# 2-_balenaFin_HAT_SCH.net
KiCad netlist of a schematic drawn in Altium Designer
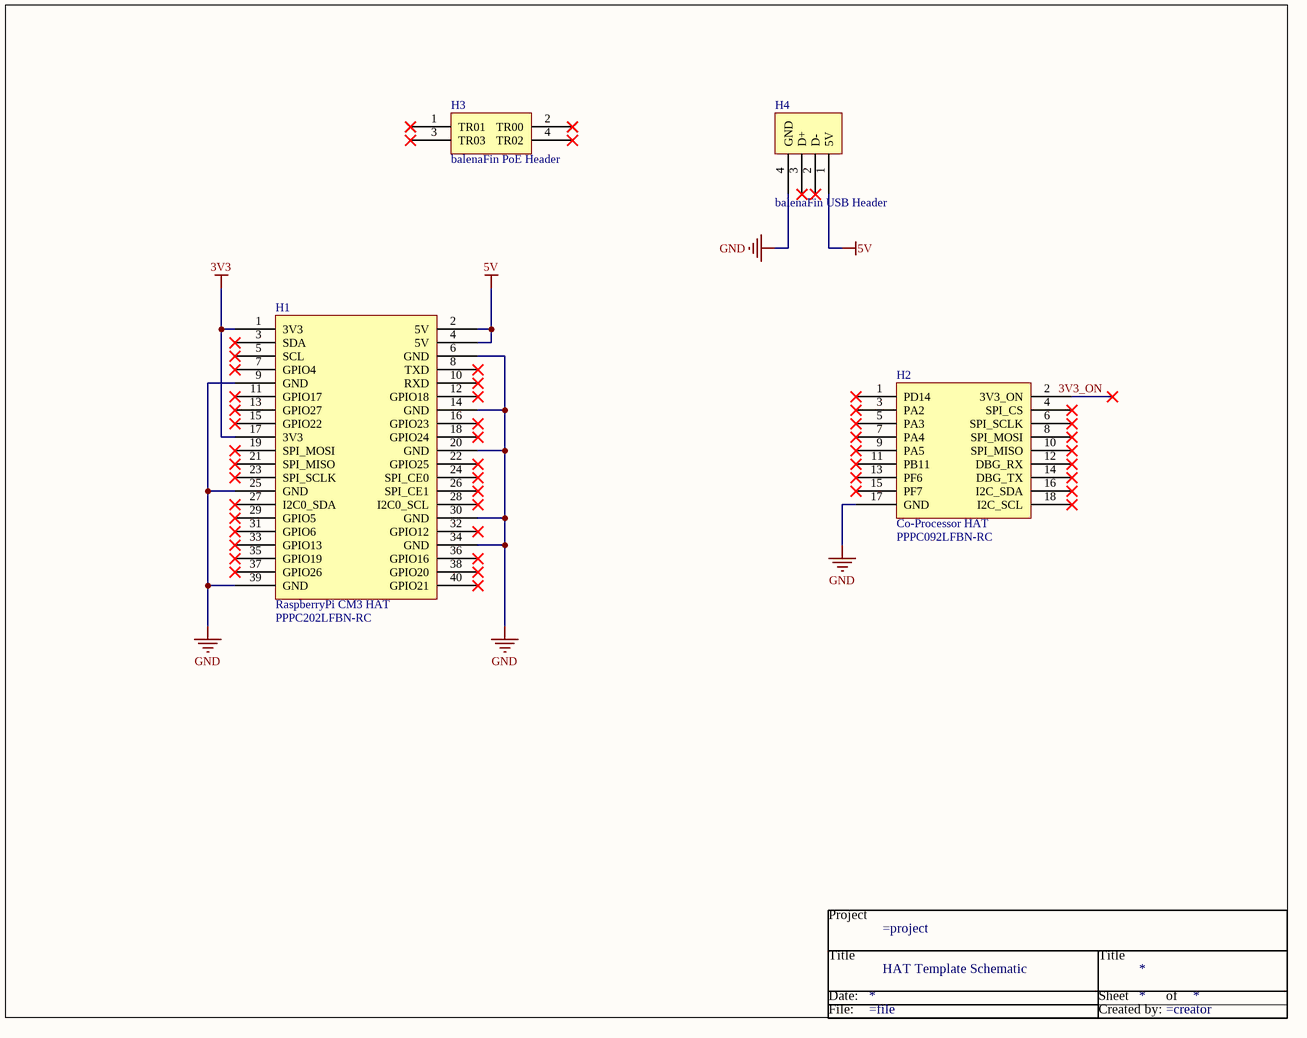
[diagram p0: 2- balenaFin HAT SCH.SchDoc]

(export (version "E")
  (design (tool "Eeschema 10.0.6"))
  (components
    (comp (ref "*") (value "Title_Block") (libsource (lib "balenaPerf schlib") (part "Title_Block")))
    (comp (ref "H1")
      (value "RaspberryPi CM3 HAT")
      (footprint "HDR2x20_2mm54")
      (description "Raspberry Pi CM3 HAT Socket")
      (fields
        (field (name "MANUFACTURER") "Sullins")
        (field (name "MANUFACTURER PART NUMBER") "PPPC202LFBN-RC")
        (field (name "SUPPLIER PART NUMBER 1") "PPPC202LFBN-RC")
      )
      (libsource (lib "balenaPerf schlib") (part "CM3_Header"))
    )
    (comp (ref "H2")
      (value "Co-Processor HAT")
      (footprint "HDR2x9_2mm54")
      (description "balenaFin Co-Processor HAT Socket")
      (fields
        (field (name "MANUFACTURER") "Sullins")
        (field (name "MANUFACTURER PART NUMBER") "PPPC092LFBN-RC")
      )
      (libsource (lib "balenaPerf schlib") (part "COP_Header"))
    )
    (comp (ref "H3")
      (value "balenaFin PoE Header")
      (footprint "HDR2x2_2mm54")
      (fields
        (field (name "MANUFACTURER") "Sullins")
        (field (name "MANUFACTURER PART NUMBER") "PPPC022LFBN-RC")
      )
      (libsource (lib "balenaPerf schlib") (part "POE_Header"))
    )
    (comp (ref "H4")
      (value "balenaFin USB Header")
      (footprint "HDR1x4_2mm54")
      (fields
        (field (name "MANUFACTURER") "Sullins")
        (field (name "MANUFACTURER PART NUMBER") "PPPC041LFBN-RC")
      )
      (libsource (lib "balenaPerf schlib") (part "USB_Header"))
    )
  )
  (nets
    (net (code "2") (name "3V3") (class "Default")
      (node (ref "H1") (pin "1") (pinfunction "3V3_1") (pintype "passive"))
      (node (ref "H1") (pin "17") (pinfunction "3V3_17") (pintype "passive"))
    )
    (net (code "3") (name "5V") (class "Default")
      (node (ref "H1") (pin "2") (pinfunction "5V_2") (pintype "passive"))
      (node (ref "H1") (pin "4") (pinfunction "5V_4") (pintype "passive"))
      (node (ref "H4") (pin "1") (pinfunction "5V_1") (pintype "passive"))
    )
    (net (code "4") (name "GND") (class "Default")
      (node (ref "H1") (pin "14") (pinfunction "GND_14") (pintype "passive"))
      (node (ref "H1") (pin "20") (pinfunction "GND_20") (pintype "passive"))
      (node (ref "H1") (pin "25") (pinfunction "GND_25") (pintype "passive"))
      (node (ref "H1") (pin "30") (pinfunction "GND_30") (pintype "passive"))
      (node (ref "H1") (pin "34") (pinfunction "GND_34") (pintype "passive"))
      (node (ref "H1") (pin "39") (pinfunction "GND_39") (pintype "passive"))
      (node (ref "H1") (pin "6") (pinfunction "GND_6") (pintype "passive"))
      (node (ref "H1") (pin "9") (pinfunction "GND_9") (pintype "passive"))
      (node (ref "H2") (pin "17") (pinfunction "GND_17") (pintype "passive"))
      (node (ref "H4") (pin "4") (pinfunction "GND_4") (pintype "passive"))
    )
    (net (code "5") (name "unconnected-(H1-GPIO4-Pad7)") (class "Default")
      (node (ref "H1") (pin "7") (pinfunction "GPIO4_7") (pintype "passive+no_connect"))
    )
    (net (code "6") (name "unconnected-(H1-GPIO5-Pad29)") (class "Default")
      (node (ref "H1") (pin "29") (pinfunction "GPIO5_29") (pintype "passive+no_connect"))
    )
    (net (code "7") (name "unconnected-(H1-GPIO6-Pad31)") (class "Default")
      (node (ref "H1") (pin "31") (pinfunction "GPIO6_31") (pintype "passive+no_connect"))
    )
    (net (code "8") (name "unconnected-(H1-GPIO12-Pad32)") (class "Default")
      (node (ref "H1") (pin "32") (pinfunction "GPIO12_32") (pintype "passive+no_connect"))
    )
    (net (code "9") (name "unconnected-(H1-GPIO13-Pad33)") (class "Default")
      (node (ref "H1") (pin "33") (pinfunction "GPIO13_33") (pintype "passive+no_connect"))
    )
    (net (code "10") (name "unconnected-(H1-GPIO16-Pad36)") (class "Default")
      (node (ref "H1") (pin "36") (pinfunction "GPIO16_36") (pintype "passive+no_connect"))
    )
    (net (code "11") (name "unconnected-(H1-GPIO17-Pad11)") (class "Default")
      (node (ref "H1") (pin "11") (pinfunction "GPIO17_11") (pintype "passive+no_connect"))
    )
    (net (code "12") (name "unconnected-(H1-GPIO18-Pad12)") (class "Default")
      (node (ref "H1") (pin "12") (pinfunction "GPIO18_12") (pintype "passive+no_connect"))
    )
    (net (code "13") (name "unconnected-(H1-GPIO19-Pad35)") (class "Default")
      (node (ref "H1") (pin "35") (pinfunction "GPIO19_35") (pintype "passive+no_connect"))
    )
    (net (code "14") (name "unconnected-(H1-GPIO20-Pad38)") (class "Default")
      (node (ref "H1") (pin "38") (pinfunction "GPIO20_38") (pintype "passive+no_connect"))
    )
    (net (code "15") (name "unconnected-(H1-GPIO21-Pad40)") (class "Default")
      (node (ref "H1") (pin "40") (pinfunction "GPIO21_40") (pintype "passive+no_connect"))
    )
    (net (code "16") (name "unconnected-(H1-GPIO22-Pad15)") (class "Default")
      (node (ref "H1") (pin "15") (pinfunction "GPIO22_15") (pintype "passive+no_connect"))
    )
    (net (code "17") (name "unconnected-(H1-GPIO23-Pad16)") (class "Default")
      (node (ref "H1") (pin "16") (pinfunction "GPIO23_16") (pintype "passive+no_connect"))
    )
    (net (code "18") (name "unconnected-(H1-GPIO24-Pad18)") (class "Default")
      (node (ref "H1") (pin "18") (pinfunction "GPIO24_18") (pintype "passive+no_connect"))
    )
    (net (code "19") (name "unconnected-(H1-GPIO25-Pad22)") (class "Default")
      (node (ref "H1") (pin "22") (pinfunction "GPIO25_22") (pintype "passive+no_connect"))
    )
    (net (code "20") (name "unconnected-(H1-GPIO26-Pad37)") (class "Default")
      (node (ref "H1") (pin "37") (pinfunction "GPIO26_37") (pintype "passive+no_connect"))
    )
    (net (code "21") (name "unconnected-(H1-GPIO27-Pad13)") (class "Default")
      (node (ref "H1") (pin "13") (pinfunction "GPIO27_13") (pintype "passive+no_connect"))
    )
    (net (code "22") (name "unconnected-(H1-I2C0_SCL-Pad28)") (class "Default")
      (node (ref "H1") (pin "28") (pinfunction "I2C0_SCL_28") (pintype "passive+no_connect"))
    )
    (net (code "23") (name "unconnected-(H1-I2C0_SDA-Pad27)") (class "Default")
      (node (ref "H1") (pin "27") (pinfunction "I2C0_SDA_27") (pintype "passive+no_connect"))
    )
    (net (code "24") (name "unconnected-(H1-RXD-Pad10)") (class "Default")
      (node (ref "H1") (pin "10") (pinfunction "RXD_10") (pintype "passive+no_connect"))
    )
    (net (code "25") (name "unconnected-(H1-SCL-Pad5)") (class "Default")
      (node (ref "H1") (pin "5") (pinfunction "SCL_5") (pintype "passive+no_connect"))
    )
    (net (code "26") (name "unconnected-(H1-SDA-Pad3)") (class "Default")
      (node (ref "H1") (pin "3") (pinfunction "SDA_3") (pintype "passive+no_connect"))
    )
    (net (code "27") (name "unconnected-(H1-SPI_CE0-Pad24)") (class "Default")
      (node (ref "H1") (pin "24") (pinfunction "SPI_CE0_24") (pintype "passive+no_connect"))
    )
    (net (code "28") (name "unconnected-(H1-SPI_CE1-Pad26)") (class "Default")
      (node (ref "H1") (pin "26") (pinfunction "SPI_CE1_26") (pintype "passive+no_connect"))
    )
    (net (code "29") (name "unconnected-(H1-SPI_MISO-Pad21)") (class "Default")
      (node (ref "H1") (pin "21") (pinfunction "SPI_MISO_21") (pintype "passive+no_connect"))
    )
    (net (code "30") (name "unconnected-(H1-SPI_MOSI-Pad19)") (class "Default")
      (node (ref "H1") (pin "19") (pinfunction "SPI_MOSI_19") (pintype "passive+no_connect"))
    )
    (net (code "31") (name "unconnected-(H1-SPI_SCLK-Pad23)") (class "Default")
      (node (ref "H1") (pin "23") (pinfunction "SPI_SCLK_23") (pintype "passive+no_connect"))
    )
    (net (code "32") (name "unconnected-(H1-TXD-Pad8)") (class "Default")
      (node (ref "H1") (pin "8") (pinfunction "TXD_8") (pintype "passive+no_connect"))
    )
    (net (code "33") (name "unconnected-(H2-3V3_ON-Pad2)") (class "Default")
      (node (ref "H2") (pin "2") (pinfunction "3V3_ON_2") (pintype "passive+no_connect"))
    )
    (net (code "34") (name "unconnected-(H2-DBG_RX-Pad12)") (class "Default")
      (node (ref "H2") (pin "12") (pinfunction "DBG_RX_12") (pintype "passive+no_connect"))
    )
    (net (code "35") (name "unconnected-(H2-DBG_TX-Pad14)") (class "Default")
      (node (ref "H2") (pin "14") (pinfunction "DBG_TX_14") (pintype "passive+no_connect"))
    )
    (net (code "36") (name "unconnected-(H2-I2C_SCL-Pad18)") (class "Default")
      (node (ref "H2") (pin "18") (pinfunction "I2C_SCL_18") (pintype "passive+no_connect"))
    )
    (net (code "37") (name "unconnected-(H2-I2C_SDA-Pad16)") (class "Default")
      (node (ref "H2") (pin "16") (pinfunction "I2C_SDA_16") (pintype "passive+no_connect"))
    )
    (net (code "38") (name "unconnected-(H2-PA2-Pad3)") (class "Default")
      (node (ref "H2") (pin "3") (pinfunction "PA2_3") (pintype "passive+no_connect"))
    )
    (net (code "39") (name "unconnected-(H2-PA3-Pad5)") (class "Default")
      (node (ref "H2") (pin "5") (pinfunction "PA3_5") (pintype "passive+no_connect"))
    )
    (net (code "40") (name "unconnected-(H2-PA4-Pad7)") (class "Default")
      (node (ref "H2") (pin "7") (pinfunction "PA4_7") (pintype "passive+no_connect"))
    )
    (net (code "41") (name "unconnected-(H2-PA5-Pad9)") (class "Default")
      (node (ref "H2") (pin "9") (pinfunction "PA5_9") (pintype "passive+no_connect"))
    )
    (net (code "42") (name "unconnected-(H2-PB11-Pad11)") (class "Default")
      (node (ref "H2") (pin "11") (pinfunction "PB11_11") (pintype "passive+no_connect"))
    )
    (net (code "43") (name "unconnected-(H2-PD14-Pad1)") (class "Default")
      (node (ref "H2") (pin "1") (pinfunction "PD14_1") (pintype "passive+no_connect"))
    )
    (net (code "44") (name "unconnected-(H2-PF6-Pad13)") (class "Default")
      (node (ref "H2") (pin "13") (pinfunction "PF6_13") (pintype "passive+no_connect"))
    )
    (net (code "45") (name "unconnected-(H2-PF7-Pad15)") (class "Default")
      (node (ref "H2") (pin "15") (pinfunction "PF7_15") (pintype "passive+no_connect"))
    )
    (net (code "46") (name "unconnected-(H2-SPI_CS-Pad4)") (class "Default")
      (node (ref "H2") (pin "4") (pinfunction "SPI_CS_4") (pintype "passive+no_connect"))
    )
    (net (code "47") (name "unconnected-(H2-SPI_MISO-Pad10)") (class "Default")
      (node (ref "H2") (pin "10") (pinfunction "SPI_MISO_10") (pintype "passive+no_connect"))
    )
    (net (code "48") (name "unconnected-(H2-SPI_MOSI-Pad8)") (class "Default")
      (node (ref "H2") (pin "8") (pinfunction "SPI_MOSI_8") (pintype "passive+no_connect"))
    )
    (net (code "49") (name "unconnected-(H2-SPI_SCLK-Pad6)") (class "Default")
      (node (ref "H2") (pin "6") (pinfunction "SPI_SCLK_6") (pintype "passive+no_connect"))
    )
    (net (code "50") (name "unconnected-(H3-TR00-Pad2)") (class "Default")
      (node (ref "H3") (pin "2") (pinfunction "TR00_2") (pintype "passive+no_connect"))
    )
    (net (code "51") (name "unconnected-(H3-TR01-Pad1)") (class "Default")
      (node (ref "H3") (pin "1") (pinfunction "TR01_1") (pintype "passive+no_connect"))
    )
    (net (code "52") (name "unconnected-(H3-TR02-Pad4)") (class "Default")
      (node (ref "H3") (pin "4") (pinfunction "TR02_4") (pintype "passive+no_connect"))
    )
    (net (code "53") (name "unconnected-(H3-TR03-Pad3)") (class "Default")
      (node (ref "H3") (pin "3") (pinfunction "TR03_3") (pintype "passive+no_connect"))
    )
    (net (code "54") (name "unconnected-(H4-D+-Pad3)") (class "Default")
      (node (ref "H4") (pin "3") (pinfunction "D+_3") (pintype "passive+no_connect"))
    )
    (net (code "55") (name "unconnected-(H4-D--Pad2)") (class "Default")
      (node (ref "H4") (pin "2") (pinfunction "D-_2") (pintype "passive+no_connect"))
    )
  )
)
